# LineSensorBoardSchematic.net
KiCad netlist of a schematic drawn in Altium Designer
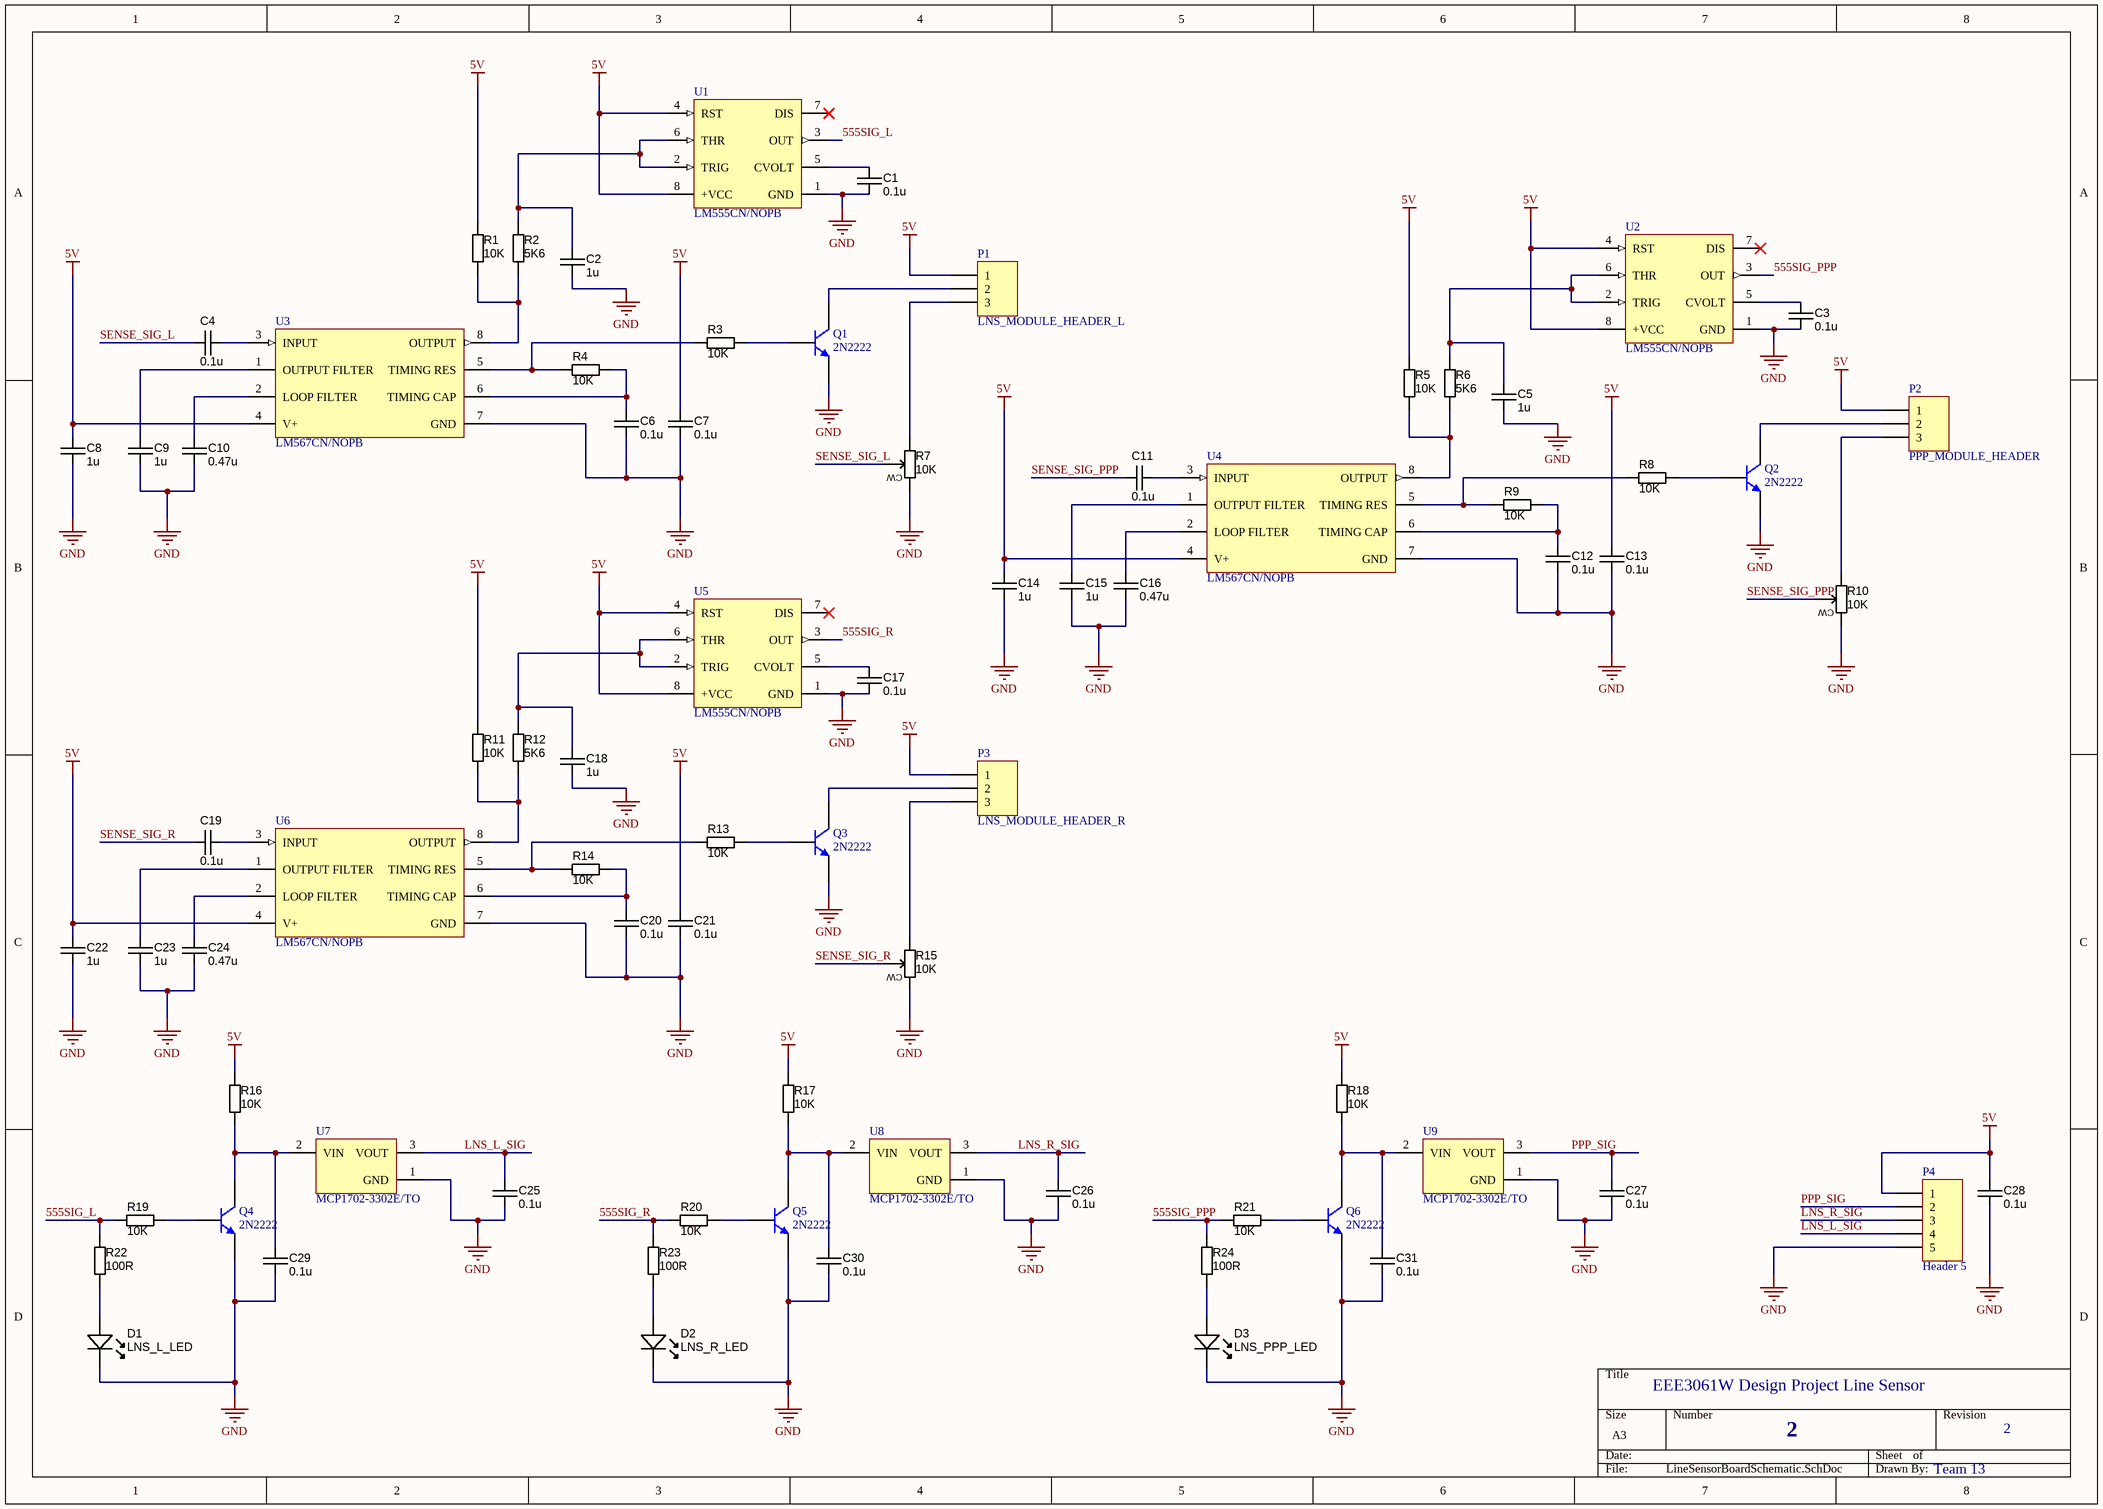
[diagram p0: LineSensorBoardSchematic.SchDoc]

(export (version "E")
  (design (tool "Eeschema 10.0.6"))
  (components
    (comp (ref "C1")
      (value "0.1u")
      (footprint "CAPC2012X135N")
      (description "Capacitor SMD Cer 1.8nF 10% 50V X7R 0805")
      (fields (field (name "TOLERANCE") "±10%") (field (name "Comment") "approved sub OK"))
      (libsource (lib "PBL - Capacitors") (part "CAPC_1n8_50V_0805"))
    )
    (comp (ref "C2")
      (value "1u")
      (footprint "CAPC2012X135N")
      (description "Capacitor SMD Cer 1.8nF 10% 50V X7R 0805")
      (fields (field (name "TOLERANCE") "±10%") (field (name "Comment") "approved sub OK"))
      (libsource (lib "PBL - Capacitors") (part "CAPC_1n8_50V_0805"))
    )
    (comp (ref "C3")
      (value "0.1u")
      (footprint "CAPC2012X135N")
      (description "Capacitor SMD Cer 1.8nF 10% 50V X7R 0805")
      (fields (field (name "TOLERANCE") "±10%") (field (name "Comment") "approved sub OK"))
      (libsource (lib "PBL - Capacitors") (part "CAPC_1n8_50V_0805"))
    )
    (comp (ref "C4")
      (value "0.1u")
      (footprint "CAPC2012X135N")
      (description "Capacitor SMD Cer 1.8nF 10% 50V X7R 0805")
      (fields (field (name "TOLERANCE") "±10%") (field (name "Comment") "approved sub OK"))
      (libsource (lib "PBL - Capacitors") (part "CAPC_1n8_50V_0805"))
    )
    (comp (ref "C5")
      (value "1u")
      (footprint "CAPC2012X135N")
      (description "Capacitor SMD Cer 1.8nF 10% 50V X7R 0805")
      (fields (field (name "TOLERANCE") "±10%") (field (name "Comment") "approved sub OK"))
      (libsource (lib "PBL - Capacitors") (part "CAPC_1n8_50V_0805"))
    )
    (comp (ref "C6")
      (value "0.1u")
      (footprint "CAPC2012X135N")
      (description "Capacitor SMD Cer 1.8nF 10% 50V X7R 0805")
      (fields (field (name "TOLERANCE") "±10%") (field (name "Comment") "approved sub OK"))
      (libsource (lib "PBL - Capacitors") (part "CAPC_1n8_50V_0805"))
    )
    (comp (ref "C7")
      (value "0.1u")
      (footprint "CAPC2012X135N")
      (description "Capacitor SMD Cer 1.8nF 10% 50V X7R 0805")
      (fields (field (name "TOLERANCE") "±10%") (field (name "Comment") "approved sub OK"))
      (libsource (lib "PBL - Capacitors") (part "CAPC_1n8_50V_0805"))
    )
    (comp (ref "C8")
      (value "1u")
      (footprint "CAPC2012X135N")
      (description "Capacitor SMD Cer 1.8nF 10% 50V X7R 0805")
      (fields (field (name "TOLERANCE") "±10%") (field (name "Comment") "approved sub OK"))
      (libsource (lib "PBL - Capacitors") (part "CAPC_1n8_50V_0805"))
    )
    (comp (ref "C9")
      (value "1u")
      (footprint "CAPC2012X135N")
      (description "Capacitor SMD Cer 1.8nF 10% 50V X7R 0805")
      (fields (field (name "TOLERANCE") "±10%") (field (name "Comment") "approved sub OK"))
      (libsource (lib "PBL - Capacitors") (part "CAPC_1n8_50V_0805"))
    )
    (comp (ref "C10")
      (value "0.47u")
      (footprint "CAPC2012X135N")
      (description "Capacitor SMD Cer 1.8nF 10% 50V X7R 0805")
      (fields (field (name "TOLERANCE") "±10%") (field (name "Comment") "approved sub OK"))
      (libsource (lib "PBL - Capacitors") (part "CAPC_1n8_50V_0805"))
    )
    (comp (ref "C11")
      (value "0.1u")
      (footprint "CAPC2012X135N")
      (description "Capacitor SMD Cer 1.8nF 10% 50V X7R 0805")
      (fields (field (name "TOLERANCE") "±10%") (field (name "Comment") "approved sub OK"))
      (libsource (lib "PBL - Capacitors") (part "CAPC_1n8_50V_0805"))
    )
    (comp (ref "C12")
      (value "0.1u")
      (footprint "CAPC2012X135N")
      (description "Capacitor SMD Cer 1.8nF 10% 50V X7R 0805")
      (fields (field (name "TOLERANCE") "±10%") (field (name "Comment") "approved sub OK"))
      (libsource (lib "PBL - Capacitors") (part "CAPC_1n8_50V_0805"))
    )
    (comp (ref "C13")
      (value "0.1u")
      (footprint "CAPC2012X135N")
      (description "Capacitor SMD Cer 1.8nF 10% 50V X7R 0805")
      (fields (field (name "TOLERANCE") "±10%") (field (name "Comment") "approved sub OK"))
      (libsource (lib "PBL - Capacitors") (part "CAPC_1n8_50V_0805"))
    )
    (comp (ref "C14")
      (value "1u")
      (footprint "CAPC2012X135N")
      (description "Capacitor SMD Cer 1.8nF 10% 50V X7R 0805")
      (fields (field (name "TOLERANCE") "±10%") (field (name "Comment") "approved sub OK"))
      (libsource (lib "PBL - Capacitors") (part "CAPC_1n8_50V_0805"))
    )
    (comp (ref "C15")
      (value "1u")
      (footprint "CAPC2012X135N")
      (description "Capacitor SMD Cer 1.8nF 10% 50V X7R 0805")
      (fields (field (name "TOLERANCE") "±10%") (field (name "Comment") "approved sub OK"))
      (libsource (lib "PBL - Capacitors") (part "CAPC_1n8_50V_0805"))
    )
    (comp (ref "C16")
      (value "0.47u")
      (footprint "CAPC2012X135N")
      (description "Capacitor SMD Cer 1.8nF 10% 50V X7R 0805")
      (fields (field (name "TOLERANCE") "±10%") (field (name "Comment") "approved sub OK"))
      (libsource (lib "PBL - Capacitors") (part "CAPC_1n8_50V_0805"))
    )
    (comp (ref "C17")
      (value "0.1u")
      (footprint "CAPC2012X135N")
      (description "Capacitor SMD Cer 1.8nF 10% 50V X7R 0805")
      (fields (field (name "TOLERANCE") "±10%") (field (name "Comment") "approved sub OK"))
      (libsource (lib "PBL - Capacitors") (part "CAPC_1n8_50V_0805"))
    )
    (comp (ref "C18")
      (value "1u")
      (footprint "CAPC2012X135N")
      (description "Capacitor SMD Cer 1.8nF 10% 50V X7R 0805")
      (fields (field (name "TOLERANCE") "±10%") (field (name "Comment") "approved sub OK"))
      (libsource (lib "PBL - Capacitors") (part "CAPC_1n8_50V_0805"))
    )
    (comp (ref "C19")
      (value "0.1u")
      (footprint "CAPC2012X135N")
      (description "Capacitor SMD Cer 1.8nF 10% 50V X7R 0805")
      (fields (field (name "TOLERANCE") "±10%") (field (name "Comment") "approved sub OK"))
      (libsource (lib "PBL - Capacitors") (part "CAPC_1n8_50V_0805"))
    )
    (comp (ref "C20")
      (value "0.1u")
      (footprint "CAPC2012X135N")
      (description "Capacitor SMD Cer 1.8nF 10% 50V X7R 0805")
      (fields (field (name "TOLERANCE") "±10%") (field (name "Comment") "approved sub OK"))
      (libsource (lib "PBL - Capacitors") (part "CAPC_1n8_50V_0805"))
    )
    (comp (ref "C21")
      (value "0.1u")
      (footprint "CAPC2012X135N")
      (description "Capacitor SMD Cer 1.8nF 10% 50V X7R 0805")
      (fields (field (name "TOLERANCE") "±10%") (field (name "Comment") "approved sub OK"))
      (libsource (lib "PBL - Capacitors") (part "CAPC_1n8_50V_0805"))
    )
    (comp (ref "C22")
      (value "1u")
      (footprint "CAPC2012X135N")
      (description "Capacitor SMD Cer 1.8nF 10% 50V X7R 0805")
      (fields (field (name "TOLERANCE") "±10%") (field (name "Comment") "approved sub OK"))
      (libsource (lib "PBL - Capacitors") (part "CAPC_1n8_50V_0805"))
    )
    (comp (ref "C23")
      (value "1u")
      (footprint "CAPC2012X135N")
      (description "Capacitor SMD Cer 1.8nF 10% 50V X7R 0805")
      (fields (field (name "TOLERANCE") "±10%") (field (name "Comment") "approved sub OK"))
      (libsource (lib "PBL - Capacitors") (part "CAPC_1n8_50V_0805"))
    )
    (comp (ref "C24")
      (value "0.47u")
      (footprint "CAPC2012X135N")
      (description "Capacitor SMD Cer 1.8nF 10% 50V X7R 0805")
      (fields (field (name "TOLERANCE") "±10%") (field (name "Comment") "approved sub OK"))
      (libsource (lib "PBL - Capacitors") (part "CAPC_1n8_50V_0805"))
    )
    (comp (ref "C25")
      (value "0.1u")
      (footprint "CAPC2012X135N")
      (description "Capacitor SMD Cer 1.8nF 10% 50V X7R 0805")
      (fields (field (name "TOLERANCE") "±10%") (field (name "Comment") "approved sub OK"))
      (libsource (lib "PBL - Capacitors") (part "CAPC_1n8_50V_0805"))
    )
    (comp (ref "C26")
      (value "0.1u")
      (footprint "CAPC2012X135N")
      (description "Capacitor SMD Cer 1.8nF 10% 50V X7R 0805")
      (fields (field (name "TOLERANCE") "±10%") (field (name "Comment") "approved sub OK"))
      (libsource (lib "PBL - Capacitors") (part "CAPC_1n8_50V_0805"))
    )
    (comp (ref "C27")
      (value "0.1u")
      (footprint "CAPC2012X135N")
      (description "Capacitor SMD Cer 1.8nF 10% 50V X7R 0805")
      (fields (field (name "TOLERANCE") "±10%") (field (name "Comment") "approved sub OK"))
      (libsource (lib "PBL - Capacitors") (part "CAPC_1n8_50V_0805"))
    )
    (comp (ref "C28")
      (value "0.1u")
      (footprint "CAPC2012X135N")
      (description "Capacitor SMD Cer 1.8nF 10% 50V X7R 0805")
      (fields (field (name "TOLERANCE") "±10%") (field (name "Comment") "approved sub OK"))
      (libsource (lib "PBL - Capacitors") (part "CAPC_1n8_50V_0805"))
    )
    (comp (ref "C29")
      (value "0.1u")
      (footprint "CAPC2012X135N")
      (description "Capacitor SMD Cer 1.8nF 10% 50V X7R 0805")
      (fields (field (name "TOLERANCE") "±10%") (field (name "Comment") "approved sub OK"))
      (libsource (lib "PBL - Capacitors") (part "CAPC_1n8_50V_0805"))
    )
    (comp (ref "C30")
      (value "0.1u")
      (footprint "CAPC2012X135N")
      (description "Capacitor SMD Cer 1.8nF 10% 50V X7R 0805")
      (fields (field (name "TOLERANCE") "±10%") (field (name "Comment") "approved sub OK"))
      (libsource (lib "PBL - Capacitors") (part "CAPC_1n8_50V_0805"))
    )
    (comp (ref "C31")
      (value "0.1u")
      (footprint "CAPC2012X135N")
      (description "Capacitor SMD Cer 1.8nF 10% 50V X7R 0805")
      (fields (field (name "TOLERANCE") "±10%") (field (name "Comment") "approved sub OK"))
      (libsource (lib "PBL - Capacitors") (part "CAPC_1n8_50V_0805"))
    )
    (comp (ref "D1")
      (value "INDLED")
      (footprint "LED-0805-K")
      (description "LED, 0805 SMD, Green")
      (fields (field (name "COLOR") "LNS_L_LED"))
      (libsource (lib "PBL - Light Sources") (part "LED_SMD_Green_0805_6mcd"))
    )
    (comp (ref "D2")
      (value "INDLED")
      (footprint "LED-0805-K")
      (description "LED, 0805 SMD, Green")
      (fields (field (name "COLOR") "LNS_R_LED"))
      (libsource (lib "PBL - Light Sources") (part "LED_SMD_Green_0805_6mcd"))
    )
    (comp (ref "D3")
      (value "INDLED")
      (footprint "LED-0805-K")
      (description "LED, 0805 SMD, Green")
      (fields (field (name "COLOR") "LNS_PPP_LED"))
      (libsource (lib "PBL - Light Sources") (part "LED_SMD_Green_0805_6mcd"))
    )
    (comp (ref "P1")
      (value "LNS_MODULE_HEADER_L")
      (footprint "HDR1X3")
      (description "Header, 3-Pin")
      (fields (field (name "PUBLISHER") "Altium Limited"))
      (libsource (lib "Miscellaneous Connectors") (part "Header 3"))
    )
    (comp (ref "P2")
      (value "PPP_MODULE_HEADER")
      (footprint "HDR1X3")
      (description "Header, 3-Pin")
      (fields (field (name "PUBLISHER") "Altium Limited"))
      (libsource (lib "Miscellaneous Connectors") (part "Header 3"))
    )
    (comp (ref "P3")
      (value "LNS_MODULE_HEADER_R")
      (footprint "HDR1X3")
      (description "Header, 3-Pin")
      (fields (field (name "PUBLISHER") "Altium Limited"))
      (libsource (lib "Miscellaneous Connectors") (part "Header 3"))
    )
    (comp (ref "P4")
      (value "Header 5")
      (footprint "HDR1X5")
      (description "Header, 5-Pin")
      (fields (field (name "PUBLISHER") "Altium Limited"))
      (libsource (lib "Miscellaneous Connectors") (part "Header 5"))
    )
    (comp (ref "Q1")
      (value "2N2222")
      (footprint "TO-226-AA")
      (description "NPN Bipolar Transistor")
      (fields (field (name "PUBLISHER") "Altium Limited"))
      (libsource (lib "Miscellaneous Devices") (part "NPN"))
    )
    (comp (ref "Q2")
      (value "2N2222")
      (footprint "TO-226-AA")
      (description "NPN Bipolar Transistor")
      (fields (field (name "PUBLISHER") "Altium Limited"))
      (libsource (lib "Miscellaneous Devices") (part "NPN"))
    )
    (comp (ref "Q3")
      (value "2N2222")
      (footprint "TO-226-AA")
      (description "NPN Bipolar Transistor")
      (fields (field (name "PUBLISHER") "Altium Limited"))
      (libsource (lib "Miscellaneous Devices") (part "NPN"))
    )
    (comp (ref "Q4")
      (value "2N2222")
      (footprint "TO-226-AA")
      (description "NPN Bipolar Transistor")
      (fields (field (name "PUBLISHER") "Altium Limited"))
      (libsource (lib "Miscellaneous Devices") (part "NPN"))
    )
    (comp (ref "Q5")
      (value "2N2222")
      (footprint "TO-226-AA")
      (description "NPN Bipolar Transistor")
      (fields (field (name "PUBLISHER") "Altium Limited"))
      (libsource (lib "Miscellaneous Devices") (part "NPN"))
    )
    (comp (ref "Q6")
      (value "2N2222")
      (footprint "TO-226-AA")
      (description "NPN Bipolar Transistor")
      (fields (field (name "PUBLISHER") "Altium Limited"))
      (libsource (lib "Miscellaneous Devices") (part "NPN"))
    )
    (comp (ref "R1")
      (value "10K")
      (footprint "RESC2012X70N")
      (description "Resistor SMD chip 150 Ohm 0.125W 5% 0805")
      (fields (field (name "TOLERANCE") "±5%") (field (name "Comment") "Thick Film"))
      (libsource (lib "") (part "RES_150R_0805_5%_2"))
    )
    (comp (ref "R2")
      (value "5K6")
      (footprint "RESC2012X70N")
      (description "Resistor SMD chip 150 Ohm 0.125W 5% 0805")
      (fields (field (name "TOLERANCE") "±5%") (field (name "Comment") "Thick Film"))
      (libsource (lib "") (part "RES_150R_0805_5%_2"))
    )
    (comp (ref "R3")
      (value "10K")
      (footprint "RESC2012X70N")
      (description "Resistor SMD chip 150 Ohm 0.125W 5% 0805")
      (fields (field (name "TOLERANCE") "±5%") (field (name "Comment") "Thick Film"))
      (libsource (lib "PBL - Resistors") (part "RES_150R_0805_5%"))
    )
    (comp (ref "R4")
      (value "10K")
      (footprint "RESC2012X70N")
      (description "Resistor SMD chip 150 Ohm 0.125W 5% 0805")
      (fields (field (name "TOLERANCE") "±5%") (field (name "Comment") "Thick Film"))
      (libsource (lib "PBL - Resistors") (part "RES_150R_0805_5%"))
    )
    (comp (ref "R5")
      (value "10K")
      (footprint "RESC2012X70N")
      (description "Resistor SMD chip 150 Ohm 0.125W 5% 0805")
      (fields (field (name "TOLERANCE") "±5%") (field (name "Comment") "Thick Film"))
      (libsource (lib "") (part "RES_150R_0805_5%_2"))
    )
    (comp (ref "R6")
      (value "5K6")
      (footprint "RESC2012X70N")
      (description "Resistor SMD chip 150 Ohm 0.125W 5% 0805")
      (fields (field (name "TOLERANCE") "±5%") (field (name "Comment") "Thick Film"))
      (libsource (lib "") (part "RES_150R_0805_5%_2"))
    )
    (comp (ref "R7")
      (value "10K")
      (footprint "POT_3306F")
      (description "Trimmer THD 10K 200mW Single-turn")
      (fields (field (name "TOLERANCE") "±25%") (field (name "Comment") "Single-turn pot"))
      (libsource (lib "PBL - Resistors") (part "RES_TRIMMER_10K_1T_THT"))
    )
    (comp (ref "R8")
      (value "10K")
      (footprint "RESC2012X70N")
      (description "Resistor SMD chip 150 Ohm 0.125W 5% 0805")
      (fields (field (name "TOLERANCE") "±5%") (field (name "Comment") "Thick Film"))
      (libsource (lib "PBL - Resistors") (part "RES_150R_0805_5%"))
    )
    (comp (ref "R9")
      (value "10K")
      (footprint "RESC2012X70N")
      (description "Resistor SMD chip 150 Ohm 0.125W 5% 0805")
      (fields (field (name "TOLERANCE") "±5%") (field (name "Comment") "Thick Film"))
      (libsource (lib "PBL - Resistors") (part "RES_150R_0805_5%"))
    )
    (comp (ref "R10")
      (value "10K")
      (footprint "POT_3306F")
      (description "Trimmer THD 10K 200mW Single-turn")
      (fields (field (name "TOLERANCE") "±25%") (field (name "Comment") "Single-turn pot"))
      (libsource (lib "PBL - Resistors") (part "RES_TRIMMER_10K_1T_THT"))
    )
    (comp (ref "R11")
      (value "10K")
      (footprint "RESC2012X70N")
      (description "Resistor SMD chip 150 Ohm 0.125W 5% 0805")
      (fields (field (name "TOLERANCE") "±5%") (field (name "Comment") "Thick Film"))
      (libsource (lib "") (part "RES_150R_0805_5%_2"))
    )
    (comp (ref "R12")
      (value "5K6")
      (footprint "RESC2012X70N")
      (description "Resistor SMD chip 150 Ohm 0.125W 5% 0805")
      (fields (field (name "TOLERANCE") "±5%") (field (name "Comment") "Thick Film"))
      (libsource (lib "") (part "RES_150R_0805_5%_2"))
    )
    (comp (ref "R13")
      (value "10K")
      (footprint "RESC2012X70N")
      (description "Resistor SMD chip 150 Ohm 0.125W 5% 0805")
      (fields (field (name "TOLERANCE") "±5%") (field (name "Comment") "Thick Film"))
      (libsource (lib "PBL - Resistors") (part "RES_150R_0805_5%"))
    )
    (comp (ref "R14")
      (value "10K")
      (footprint "RESC2012X70N")
      (description "Resistor SMD chip 150 Ohm 0.125W 5% 0805")
      (fields (field (name "TOLERANCE") "±5%") (field (name "Comment") "Thick Film"))
      (libsource (lib "PBL - Resistors") (part "RES_150R_0805_5%"))
    )
    (comp (ref "R15")
      (value "10K")
      (footprint "POT_3306F")
      (description "Trimmer THD 10K 200mW Single-turn")
      (fields (field (name "TOLERANCE") "±25%") (field (name "Comment") "Single-turn pot"))
      (libsource (lib "PBL - Resistors") (part "RES_TRIMMER_10K_1T_THT"))
    )
    (comp (ref "R16")
      (value "10K")
      (footprint "RESC2012X70N")
      (description "Resistor SMD chip 150 Ohm 0.125W 5% 0805")
      (fields (field (name "TOLERANCE") "±5%") (field (name "Comment") "Thick Film"))
      (libsource (lib "") (part "RES_150R_0805_5%_1"))
    )
    (comp (ref "R17")
      (value "10K")
      (footprint "RESC2012X70N")
      (description "Resistor SMD chip 150 Ohm 0.125W 5% 0805")
      (fields (field (name "TOLERANCE") "±5%") (field (name "Comment") "Thick Film"))
      (libsource (lib "") (part "RES_150R_0805_5%_1"))
    )
    (comp (ref "R18")
      (value "10K")
      (footprint "RESC2012X70N")
      (description "Resistor SMD chip 150 Ohm 0.125W 5% 0805")
      (fields (field (name "TOLERANCE") "±5%") (field (name "Comment") "Thick Film"))
      (libsource (lib "") (part "RES_150R_0805_5%_1"))
    )
    (comp (ref "R19")
      (value "10K")
      (footprint "RESC2012X70N")
      (description "Resistor SMD chip 150 Ohm 0.125W 5% 0805")
      (fields (field (name "TOLERANCE") "±5%") (field (name "Comment") "Thick Film"))
      (libsource (lib "PBL - Resistors") (part "RES_150R_0805_5%"))
    )
    (comp (ref "R20")
      (value "10K")
      (footprint "RESC2012X70N")
      (description "Resistor SMD chip 150 Ohm 0.125W 5% 0805")
      (fields (field (name "TOLERANCE") "±5%") (field (name "Comment") "Thick Film"))
      (libsource (lib "PBL - Resistors") (part "RES_150R_0805_5%"))
    )
    (comp (ref "R21")
      (value "10K")
      (footprint "RESC2012X70N")
      (description "Resistor SMD chip 150 Ohm 0.125W 5% 0805")
      (fields (field (name "TOLERANCE") "±5%") (field (name "Comment") "Thick Film"))
      (libsource (lib "PBL - Resistors") (part "RES_150R_0805_5%"))
    )
    (comp (ref "R22")
      (value "100R")
      (footprint "RESC2012X70N")
      (description "Resistor SMD chip 150 Ohm 0.125W 5% 0805")
      (fields (field (name "TOLERANCE") "±5%") (field (name "Comment") "Thick Film"))
      (libsource (lib "") (part "RES_150R_0805_5%_1"))
    )
    (comp (ref "R23")
      (value "100R")
      (footprint "RESC2012X70N")
      (description "Resistor SMD chip 150 Ohm 0.125W 5% 0805")
      (fields (field (name "TOLERANCE") "±5%") (field (name "Comment") "Thick Film"))
      (libsource (lib "") (part "RES_150R_0805_5%_1"))
    )
    (comp (ref "R24")
      (value "100R")
      (footprint "RESC2012X70N")
      (description "Resistor SMD chip 150 Ohm 0.125W 5% 0805")
      (fields (field (name "TOLERANCE") "±5%") (field (name "Comment") "Thick Film"))
      (libsource (lib "") (part "RES_150R_0805_5%_1"))
    )
    (comp (ref "U1")
      (value "LM555CN/NOPB")
      (footprint "N08E")
      (description "Timer, 8-pin MDIP, Pb-Free")
      (fields (field (name "MANUFACTURER") "National Semiconductor"))
      (libsource (lib "Altium Content Vault") (part "AN-TIMER-LM555-8"))
    )
    (comp (ref "U2")
      (value "LM555CN/NOPB")
      (footprint "N08E")
      (description "Timer, 8-pin MDIP, Pb-Free")
      (fields (field (name "MANUFACTURER") "National Semiconductor"))
      (libsource (lib "Altium Content Vault") (part "AN-TIMER-LM555-8"))
    )
    (comp (ref "U3")
      (value "LM567CN/NOPB")
      (footprint "N08E")
      (description "Tone Decoder, 8-pin MDIP, Pb-Free")
      (fields (field (name "MANUFACTURER") "National Semiconductor"))
      (libsource (lib "Altium Content Vault") (part "LO-DEC-LM567C-8"))
    )
    (comp (ref "U4")
      (value "LM567CN/NOPB")
      (footprint "N08E")
      (description "Tone Decoder, 8-pin MDIP, Pb-Free")
      (fields (field (name "MANUFACTURER") "National Semiconductor"))
      (libsource (lib "Altium Content Vault") (part "LO-DEC-LM567C-8"))
    )
    (comp (ref "U5")
      (value "LM555CN/NOPB")
      (footprint "N08E")
      (description "Timer, 8-pin MDIP, Pb-Free")
      (fields (field (name "MANUFACTURER") "National Semiconductor"))
      (libsource (lib "Altium Content Vault") (part "AN-TIMER-LM555-8"))
    )
    (comp (ref "U6")
      (value "LM567CN/NOPB")
      (footprint "N08E")
      (description "Tone Decoder, 8-pin MDIP, Pb-Free")
      (fields (field (name "MANUFACTURER") "National Semiconductor"))
      (libsource (lib "Altium Content Vault") (part "LO-DEC-LM567C-8"))
    )
    (comp (ref "U7")
      (value "MCP1702-3302E/TO")
      (footprint "TO-92-TO3")
      (description "250 mA Low Quiescent Current LDO Regulator, 3-Pin TO-92, Extended TemperatureBAG")
      (libsource (lib "Altium Content Vault") (part "CMP-0136-00017-1"))
    )
    (comp (ref "U8")
      (value "MCP1702-3302E/TO")
      (footprint "TO-92-TO3")
      (description "250 mA Low Quiescent Current LDO Regulator, 3-Pin TO-92, Extended TemperatureBAG")
      (libsource (lib "Altium Content Vault") (part "CMP-0136-00017-1"))
    )
    (comp (ref "U9")
      (value "MCP1702-3302E/TO")
      (footprint "TO-92-TO3")
      (description "250 mA Low Quiescent Current LDO Regulator, 3-Pin TO-92, Extended TemperatureBAG")
      (libsource (lib "Altium Content Vault") (part "CMP-0136-00017-1"))
    )
  )
  (nets
    (net (code "1") (name "/555SIG_L") (class "Default")
      (node (ref "R19") (pin "1") (pinfunction "1_1") (pintype "passive"))
      (node (ref "R22") (pin "2") (pinfunction "2_2") (pintype "passive"))
      (node (ref "U1") (pin "3") (pinfunction "OUT_3") (pintype "output"))
    )
    (net (code "2") (name "/555SIG_PPP") (class "Default")
      (node (ref "R21") (pin "1") (pinfunction "1_1") (pintype "passive"))
      (node (ref "R24") (pin "2") (pinfunction "2_2") (pintype "passive"))
      (node (ref "U2") (pin "3") (pinfunction "OUT_3") (pintype "output"))
    )
    (net (code "3") (name "/555SIG_R") (class "Default")
      (node (ref "R20") (pin "1") (pinfunction "1_1") (pintype "passive"))
      (node (ref "R23") (pin "2") (pinfunction "2_2") (pintype "passive"))
      (node (ref "U5") (pin "3") (pinfunction "OUT_3") (pintype "output"))
    )
    (net (code "4") (name "/LNS_L_SIG") (class "Default")
      (node (ref "C25") (pin "1") (pintype "passive"))
      (node (ref "P4") (pin "4") (pinfunction "4_4") (pintype "passive"))
      (node (ref "U7") (pin "3") (pinfunction "VOUT_3") (pintype "power_in"))
    )
    (net (code "5") (name "/LNS_R_SIG") (class "Default")
      (node (ref "C26") (pin "1") (pintype "passive"))
      (node (ref "P4") (pin "3") (pinfunction "3_3") (pintype "passive"))
      (node (ref "U8") (pin "3") (pinfunction "VOUT_3") (pintype "power_in"))
    )
    (net (code "6") (name "/PPP_SIG") (class "Default")
      (node (ref "C27") (pin "1") (pintype "passive"))
      (node (ref "P4") (pin "2") (pinfunction "2_2") (pintype "passive"))
      (node (ref "U9") (pin "3") (pinfunction "VOUT_3") (pintype "power_in"))
    )
    (net (code "7") (name "/SENSE_SIG_L") (class "Default")
      (node (ref "C4") (pin "2") (pintype "passive"))
      (node (ref "R7") (pin "W") (pinfunction "2_W") (pintype "passive"))
    )
    (net (code "8") (name "/SENSE_SIG_PPP") (class "Default")
      (node (ref "C11") (pin "2") (pintype "passive"))
      (node (ref "R10") (pin "W") (pinfunction "2_W") (pintype "passive"))
    )
    (net (code "9") (name "/SENSE_SIG_R") (class "Default")
      (node (ref "C19") (pin "2") (pintype "passive"))
      (node (ref "R15") (pin "W") (pinfunction "2_W") (pintype "passive"))
    )
    (net (code "10") (name "5V") (class "Default")
      (node (ref "C13") (pin "1") (pintype "passive"))
      (node (ref "C14") (pin "1") (pintype "passive"))
      (node (ref "C21") (pin "1") (pintype "passive"))
      (node (ref "C22") (pin "1") (pintype "passive"))
      (node (ref "C28") (pin "1") (pintype "passive"))
      (node (ref "C7") (pin "1") (pintype "passive"))
      (node (ref "C8") (pin "1") (pintype "passive"))
      (node (ref "P1") (pin "1") (pinfunction "1_1") (pintype "passive"))
      (node (ref "P2") (pin "1") (pinfunction "1_1") (pintype "passive"))
      (node (ref "P3") (pin "1") (pinfunction "1_1") (pintype "passive"))
      (node (ref "P4") (pin "1") (pinfunction "1_1") (pintype "passive"))
      (node (ref "R1") (pin "1") (pinfunction "1_1") (pintype "passive"))
      (node (ref "R11") (pin "1") (pinfunction "1_1") (pintype "passive"))
      (node (ref "R16") (pin "2") (pinfunction "2_2") (pintype "passive"))
      (node (ref "R17") (pin "2") (pinfunction "2_2") (pintype "passive"))
      (node (ref "R18") (pin "2") (pinfunction "2_2") (pintype "passive"))
      (node (ref "R5") (pin "1") (pinfunction "1_1") (pintype "passive"))
      (node (ref "U1") (pin "4") (pinfunction "RST_4") (pintype "input"))
      (node (ref "U1") (pin "8") (pinfunction "+VCC_8") (pintype "power_in"))
      (node (ref "U2") (pin "4") (pinfunction "RST_4") (pintype "input"))
      (node (ref "U2") (pin "8") (pinfunction "+VCC_8") (pintype "power_in"))
      (node (ref "U3") (pin "4") (pinfunction "V+_4") (pintype "power_in"))
      (node (ref "U4") (pin "4") (pinfunction "V+_4") (pintype "power_in"))
      (node (ref "U5") (pin "4") (pinfunction "RST_4") (pintype "input"))
      (node (ref "U5") (pin "8") (pinfunction "+VCC_8") (pintype "power_in"))
      (node (ref "U6") (pin "4") (pinfunction "V+_4") (pintype "power_in"))
    )
    (net (code "11") (name "GND") (class "Default")
      (node (ref "C1") (pin "2") (pintype "passive"))
      (node (ref "C10") (pin "2") (pintype "passive"))
      (node (ref "C12") (pin "2") (pintype "passive"))
      (node (ref "C13") (pin "2") (pintype "passive"))
      (node (ref "C14") (pin "2") (pintype "passive"))
      (node (ref "C15") (pin "2") (pintype "passive"))
      (node (ref "C16") (pin "2") (pintype "passive"))
      (node (ref "C17") (pin "2") (pintype "passive"))
      (node (ref "C18") (pin "2") (pintype "passive"))
      (node (ref "C2") (pin "2") (pintype "passive"))
      (node (ref "C20") (pin "2") (pintype "passive"))
      (node (ref "C21") (pin "2") (pintype "passive"))
      (node (ref "C22") (pin "2") (pintype "passive"))
      (node (ref "C23") (pin "2") (pintype "passive"))
      (node (ref "C24") (pin "2") (pintype "passive"))
      (node (ref "C25") (pin "2") (pintype "passive"))
      (node (ref "C26") (pin "2") (pintype "passive"))
      (node (ref "C27") (pin "2") (pintype "passive"))
      (node (ref "C28") (pin "2") (pintype "passive"))
      (node (ref "C29") (pin "2") (pintype "passive"))
      (node (ref "C3") (pin "2") (pintype "passive"))
      (node (ref "C30") (pin "2") (pintype "passive"))
      (node (ref "C31") (pin "2") (pintype "passive"))
      (node (ref "C5") (pin "2") (pintype "passive"))
      (node (ref "C6") (pin "2") (pintype "passive"))
      (node (ref "C7") (pin "2") (pintype "passive"))
      (node (ref "C8") (pin "2") (pintype "passive"))
      (node (ref "C9") (pin "2") (pintype "passive"))
      (node (ref "D1") (pin "K") (pinfunction "K_K") (pintype "passive"))
      (node (ref "D2") (pin "K") (pinfunction "K_K") (pintype "passive"))
      (node (ref "D3") (pin "K") (pinfunction "K_K") (pintype "passive"))
      (node (ref "P4") (pin "5") (pinfunction "5_5") (pintype "passive"))
      (node (ref "Q1") (pin "3") (pinfunction "E_3") (pintype "passive"))
      (node (ref "Q2") (pin "3") (pinfunction "E_3") (pintype "passive"))
      (node (ref "Q3") (pin "3") (pinfunction "E_3") (pintype "passive"))
      (node (ref "Q4") (pin "3") (pinfunction "E_3") (pintype "passive"))
      (node (ref "Q5") (pin "3") (pinfunction "E_3") (pintype "passive"))
      (node (ref "Q6") (pin "3") (pinfunction "E_3") (pintype "passive"))
      (node (ref "R10") (pin "CW") (pinfunction "3_CW") (pintype "passive"))
      (node (ref "R15") (pin "CW") (pinfunction "3_CW") (pintype "passive"))
      (node (ref "R7") (pin "CW") (pinfunction "3_CW") (pintype "passive"))
      (node (ref "U1") (pin "1") (pinfunction "GND_1") (pintype "power_in"))
      (node (ref "U2") (pin "1") (pinfunction "GND_1") (pintype "power_in"))
      (node (ref "U3") (pin "7") (pinfunction "GND_7") (pintype "power_in"))
      (node (ref "U4") (pin "7") (pinfunction "GND_7") (pintype "power_in"))
      (node (ref "U5") (pin "1") (pinfunction "GND_1") (pintype "power_in"))
      (node (ref "U6") (pin "7") (pinfunction "GND_7") (pintype "power_in"))
      (node (ref "U7") (pin "1") (pinfunction "GND_1") (pintype "power_in"))
      (node (ref "U8") (pin "1") (pinfunction "GND_1") (pintype "power_in"))
      (node (ref "U9") (pin "1") (pinfunction "GND_1") (pintype "power_in"))
    )
    (net (code "12") (name "Net-(D1-PadA)") (class "Default")
      (node (ref "D1") (pin "A") (pinfunction "A_A") (pintype "passive"))
      (node (ref "R22") (pin "1") (pinfunction "1_1") (pintype "passive"))
    )
    (net (code "13") (name "Net-(D2-PadA)") (class "Default")
      (node (ref "D2") (pin "A") (pinfunction "A_A") (pintype "passive"))
      (node (ref "R23") (pin "1") (pinfunction "1_1") (pintype "passive"))
    )
    (net (code "14") (name "Net-(D3-PadA)") (class "Default")
      (node (ref "D3") (pin "A") (pinfunction "A_A") (pintype "passive"))
      (node (ref "R24") (pin "1") (pinfunction "1_1") (pintype "passive"))
    )
    (net (code "15") (name "Net-(Q1-B)") (class "Default")
      (node (ref "Q1") (pin "2") (pinfunction "B_2") (pintype "passive"))
      (node (ref "R3") (pin "2") (pinfunction "2_2") (pintype "passive"))
    )
    (net (code "16") (name "Net-(Q1-C)") (class "Default")
      (node (ref "P1") (pin "2") (pinfunction "2_2") (pintype "passive"))
      (node (ref "Q1") (pin "1") (pinfunction "C_1") (pintype "passive"))
    )
    (net (code "17") (name "Net-(Q2-B)") (class "Default")
      (node (ref "Q2") (pin "2") (pinfunction "B_2") (pintype "passive"))
      (node (ref "R8") (pin "2") (pinfunction "2_2") (pintype "passive"))
    )
    (net (code "18") (name "Net-(Q2-C)") (class "Default")
      (node (ref "P2") (pin "2") (pinfunction "2_2") (pintype "passive"))
      (node (ref "Q2") (pin "1") (pinfunction "C_1") (pintype "passive"))
    )
    (net (code "19") (name "Net-(Q3-B)") (class "Default")
      (node (ref "Q3") (pin "2") (pinfunction "B_2") (pintype "passive"))
      (node (ref "R13") (pin "2") (pinfunction "2_2") (pintype "passive"))
    )
    (net (code "20") (name "Net-(Q3-C)") (class "Default")
      (node (ref "P3") (pin "2") (pinfunction "2_2") (pintype "passive"))
      (node (ref "Q3") (pin "1") (pinfunction "C_1") (pintype "passive"))
    )
    (net (code "21") (name "Net-(Q4-B)") (class "Default")
      (node (ref "Q4") (pin "2") (pinfunction "B_2") (pintype "passive"))
      (node (ref "R19") (pin "2") (pinfunction "2_2") (pintype "passive"))
    )
    (net (code "22") (name "Net-(Q4-C)") (class "Default")
      (node (ref "C29") (pin "1") (pintype "passive"))
      (node (ref "Q4") (pin "1") (pinfunction "C_1") (pintype "passive"))
      (node (ref "R16") (pin "1") (pinfunction "1_1") (pintype "passive"))
      (node (ref "U7") (pin "2") (pinfunction "VIN_2") (pintype "power_in"))
    )
    (net (code "23") (name "Net-(Q5-B)") (class "Default")
      (node (ref "Q5") (pin "2") (pinfunction "B_2") (pintype "passive"))
      (node (ref "R20") (pin "2") (pinfunction "2_2") (pintype "passive"))
    )
    (net (code "24") (name "Net-(Q5-C)") (class "Default")
      (node (ref "C30") (pin "1") (pintype "passive"))
      (node (ref "Q5") (pin "1") (pinfunction "C_1") (pintype "passive"))
      (node (ref "R17") (pin "1") (pinfunction "1_1") (pintype "passive"))
      (node (ref "U8") (pin "2") (pinfunction "VIN_2") (pintype "power_in"))
    )
    (net (code "25") (name "Net-(Q6-B)") (class "Default")
      (node (ref "Q6") (pin "2") (pinfunction "B_2") (pintype "passive"))
      (node (ref "R21") (pin "2") (pinfunction "2_2") (pintype "passive"))
    )
    (net (code "26") (name "Net-(Q6-C)") (class "Default")
      (node (ref "C31") (pin "1") (pintype "passive"))
      (node (ref "Q6") (pin "1") (pinfunction "C_1") (pintype "passive"))
      (node (ref "R18") (pin "1") (pinfunction "1_1") (pintype "passive"))
      (node (ref "U9") (pin "2") (pinfunction "VIN_2") (pintype "power_in"))
    )
    (net (code "27") (name "Net-(R7-1)") (class "Default")
      (node (ref "P1") (pin "3") (pinfunction "3_3") (pintype "passive"))
      (node (ref "R7") (pin "CCW") (pinfunction "1_CCW") (pintype "passive"))
    )
    (net (code "28") (name "Net-(R10-1)") (class "Default")
      (node (ref "P2") (pin "3") (pinfunction "3_3") (pintype "passive"))
      (node (ref "R10") (pin "CCW") (pinfunction "1_CCW") (pintype "passive"))
    )
    (net (code "29") (name "Net-(R15-1)") (class "Default")
      (node (ref "P3") (pin "3") (pinfunction "3_3") (pintype "passive"))
      (node (ref "R15") (pin "CCW") (pinfunction "1_CCW") (pintype "passive"))
    )
    (net (code "30") (name "Net-(U1-CVOLT)") (class "Default")
      (node (ref "C1") (pin "1") (pintype "passive"))
      (node (ref "U1") (pin "5") (pinfunction "CVOLT_5") (pintype "passive"))
    )
    (net (code "31") (name "Net-(U1-THR)") (class "Default")
      (node (ref "C2") (pin "1") (pintype "passive"))
      (node (ref "R2") (pin "1") (pinfunction "1_1") (pintype "passive"))
      (node (ref "U1") (pin "2") (pinfunction "TRIG_2") (pintype "input"))
      (node (ref "U1") (pin "6") (pinfunction "THR_6") (pintype "input"))
    )
    (net (code "32") (name "Net-(U2-CVOLT)") (class "Default")
      (node (ref "C3") (pin "1") (pintype "passive"))
      (node (ref "U2") (pin "5") (pinfunction "CVOLT_5") (pintype "passive"))
    )
    (net (code "33") (name "Net-(U2-THR)") (class "Default")
      (node (ref "C5") (pin "1") (pintype "passive"))
      (node (ref "R6") (pin "1") (pinfunction "1_1") (pintype "passive"))
      (node (ref "U2") (pin "2") (pinfunction "TRIG_2") (pintype "input"))
      (node (ref "U2") (pin "6") (pinfunction "THR_6") (pintype "input"))
    )
    (net (code "34") (name "Net-(U3-INPUT)") (class "Default")
      (node (ref "C4") (pin "1") (pintype "passive"))
      (node (ref "U3") (pin "3") (pinfunction "INPUT_3") (pintype "input"))
    )
    (net (code "35") (name "Net-(U3-LOOP_FILTER)") (class "Default")
      (node (ref "C10") (pin "1") (pintype "passive"))
      (node (ref "U3") (pin "2") (pinfunction "LOOP_FILTER_2") (pintype "passive"))
    )
    (net (code "36") (name "Net-(U3-OUTPUT)") (class "Default")
      (node (ref "R1") (pin "2") (pinfunction "2_2") (pintype "passive"))
      (node (ref "R2") (pin "2") (pinfunction "2_2") (pintype "passive"))
      (node (ref "U3") (pin "8") (pinfunction "OUTPUT_8") (pintype "output"))
    )
    (net (code "37") (name "Net-(U3-OUTPUT_FILTER)") (class "Default")
      (node (ref "C9") (pin "1") (pintype "passive"))
      (node (ref "U3") (pin "1") (pinfunction "OUTPUT_FILTER_1") (pintype "passive"))
    )
    (net (code "38") (name "Net-(U3-TIMING_CAP)") (class "Default")
      (node (ref "C6") (pin "1") (pintype "passive"))
      (node (ref "R4") (pin "2") (pinfunction "2_2") (pintype "passive"))
      (node (ref "U3") (pin "6") (pinfunction "TIMING_CAP_6") (pintype "passive"))
    )
    (net (code "39") (name "Net-(U3-TIMING_RES)") (class "Default")
      (node (ref "R3") (pin "1") (pinfunction "1_1") (pintype "passive"))
      (node (ref "R4") (pin "1") (pinfunction "1_1") (pintype "passive"))
      (node (ref "U3") (pin "5") (pinfunction "TIMING_RES_5") (pintype "passive"))
    )
    (net (code "40") (name "Net-(U4-INPUT)") (class "Default")
      (node (ref "C11") (pin "1") (pintype "passive"))
      (node (ref "U4") (pin "3") (pinfunction "INPUT_3") (pintype "input"))
    )
    (net (code "41") (name "Net-(U4-LOOP_FILTER)") (class "Default")
      (node (ref "C16") (pin "1") (pintype "passive"))
      (node (ref "U4") (pin "2") (pinfunction "LOOP_FILTER_2") (pintype "passive"))
    )
    (net (code "42") (name "Net-(U4-OUTPUT)") (class "Default")
      (node (ref "R5") (pin "2") (pinfunction "2_2") (pintype "passive"))
      (node (ref "R6") (pin "2") (pinfunction "2_2") (pintype "passive"))
      (node (ref "U4") (pin "8") (pinfunction "OUTPUT_8") (pintype "output"))
    )
    (net (code "43") (name "Net-(U4-OUTPUT_FILTER)") (class "Default")
      (node (ref "C15") (pin "1") (pintype "passive"))
      (node (ref "U4") (pin "1") (pinfunction "OUTPUT_FILTER_1") (pintype "passive"))
    )
    (net (code "44") (name "Net-(U4-TIMING_CAP)") (class "Default")
      (node (ref "C12") (pin "1") (pintype "passive"))
      (node (ref "R9") (pin "2") (pinfunction "2_2") (pintype "passive"))
      (node (ref "U4") (pin "6") (pinfunction "TIMING_CAP_6") (pintype "passive"))
    )
    (net (code "45") (name "Net-(U4-TIMING_RES)") (class "Default")
      (node (ref "R8") (pin "1") (pinfunction "1_1") (pintype "passive"))
      (node (ref "R9") (pin "1") (pinfunction "1_1") (pintype "passive"))
      (node (ref "U4") (pin "5") (pinfunction "TIMING_RES_5") (pintype "passive"))
    )
    (net (code "46") (name "Net-(U5-CVOLT)") (class "Default")
      (node (ref "C17") (pin "1") (pintype "passive"))
      (node (ref "U5") (pin "5") (pinfunction "CVOLT_5") (pintype "passive"))
    )
    (net (code "47") (name "Net-(U5-THR)") (class "Default")
      (node (ref "C18") (pin "1") (pintype "passive"))
      (node (ref "R12") (pin "1") (pinfunction "1_1") (pintype "passive"))
      (node (ref "U5") (pin "2") (pinfunction "TRIG_2") (pintype "input"))
      (node (ref "U5") (pin "6") (pinfunction "THR_6") (pintype "input"))
    )
    (net (code "48") (name "Net-(U6-INPUT)") (class "Default")
      (node (ref "C19") (pin "1") (pintype "passive"))
      (node (ref "U6") (pin "3") (pinfunction "INPUT_3") (pintype "input"))
    )
    (net (code "49") (name "Net-(U6-LOOP_FILTER)") (class "Default")
      (node (ref "C24") (pin "1") (pintype "passive"))
      (node (ref "U6") (pin "2") (pinfunction "LOOP_FILTER_2") (pintype "passive"))
    )
    (net (code "50") (name "Net-(U6-OUTPUT)") (class "Default")
      (node (ref "R11") (pin "2") (pinfunction "2_2") (pintype "passive"))
      (node (ref "R12") (pin "2") (pinfunction "2_2") (pintype "passive"))
      (node (ref "U6") (pin "8") (pinfunction "OUTPUT_8") (pintype "output"))
    )
    (net (code "51") (name "Net-(U6-OUTPUT_FILTER)") (class "Default")
      (node (ref "C23") (pin "1") (pintype "passive"))
      (node (ref "U6") (pin "1") (pinfunction "OUTPUT_FILTER_1") (pintype "passive"))
    )
    (net (code "52") (name "Net-(U6-TIMING_CAP)") (class "Default")
      (node (ref "C20") (pin "1") (pintype "passive"))
      (node (ref "R14") (pin "2") (pinfunction "2_2") (pintype "passive"))
      (node (ref "U6") (pin "6") (pinfunction "TIMING_CAP_6") (pintype "passive"))
    )
    (net (code "53") (name "Net-(U6-TIMING_RES)") (class "Default")
      (node (ref "R13") (pin "1") (pinfunction "1_1") (pintype "passive"))
      (node (ref "R14") (pin "1") (pinfunction "1_1") (pintype "passive"))
      (node (ref "U6") (pin "5") (pinfunction "TIMING_RES_5") (pintype "passive"))
    )
    (net (code "54") (name "unconnected-(U1-DIS-Pad7)") (class "Default")
      (node (ref "U1") (pin "7") (pinfunction "DIS_7") (pintype "open_collector+no_connect"))
    )
    (net (code "55") (name "unconnected-(U2-DIS-Pad7)") (class "Default")
      (node (ref "U2") (pin "7") (pinfunction "DIS_7") (pintype "open_collector+no_connect"))
    )
    (net (code "56") (name "unconnected-(U5-DIS-Pad7)") (class "Default")
      (node (ref "U5") (pin "7") (pinfunction "DIS_7") (pintype "open_collector+no_connect"))
    )
  )
)
